# AT89S52_2.net
KiCad netlist of a schematic drawn in Altium Designer
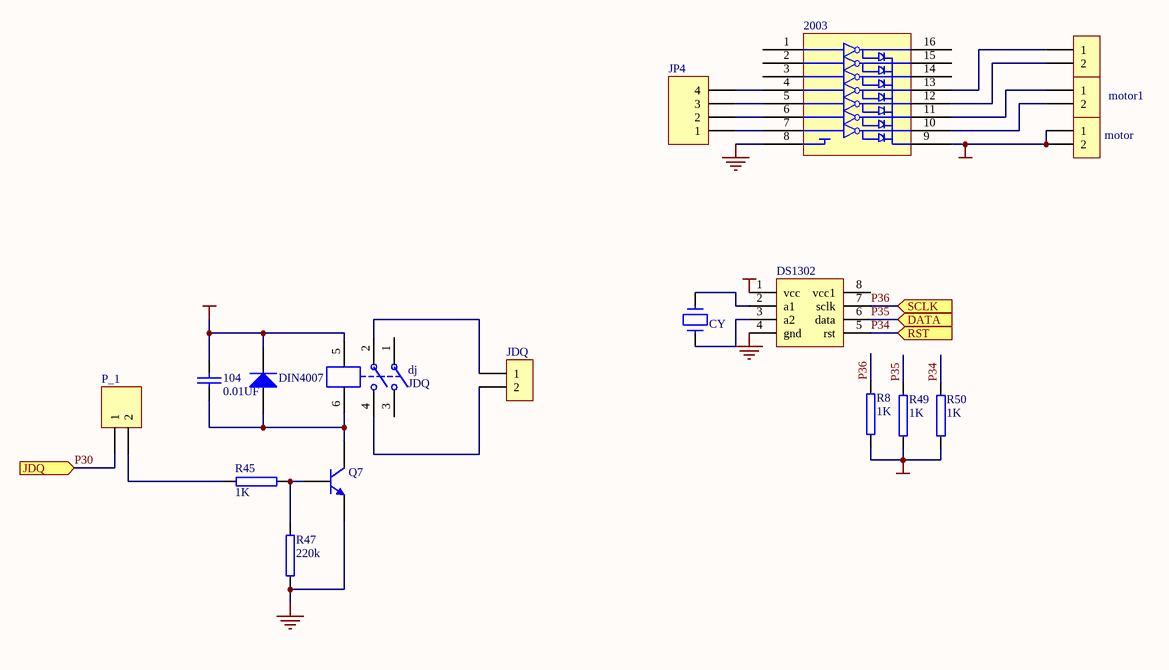
[diagram p0: AT89S52多功能板2.SchDoc]

(export (version "E")
  (design (tool "Eeschema 10.0.6"))
  (components
    (comp (ref "104")
      (value "0.01UF")
      (footprint "RAD0.3")
      (description "Capacitor")
      (libsource (lib "OldCow1 (1)") (part "CAP"))
    )
    (comp (ref "121") (value "CY") (footprint "CYPF") (libsource (lib "OldCow1 (1)") (part "CY")))
    (comp (ref "2003") (value "2003") (footprint "2003PF") (libsource (lib "OldCow1 (1)") (part "2003")))
    (comp (ref "DIN4007")
      (value "Diode 1N4007")
      (footprint "DO-41")
      (description "1 Amp General Purpose Rectifier")
      (fields (field (name "PUBLISHER") "Altium Limited"))
      (libsource (lib "Miscellaneous Devices") (part "Diode 1N4007"))
    )
    (comp (ref "dj") (value "JDQ") (footprint "JDQPF") (libsource (lib "OldCow1 (1)") (part "JDQ")))
    (comp (ref "DS1302") (value "DS1302") (footprint "DIP8") (libsource (lib "OldCow1 (1)") (part "DS1302")))
    (comp (ref "JDQ") (value "POWER") (footprint "POWERPF") (libsource (lib "OldCow1 (1)") (part "POWER")))
    (comp (ref "JP4")
      (value "Header 4")
      (footprint "HDR1X4")
      (description "Header, 4-Pin")
      (fields (field (name "PUBLISHER") "Altium Limited"))
      (libsource (lib "Miscellaneous Connectors") (part "Header 4"))
    )
    (comp (ref "motor") (value "POWER") (footprint "POWERPF") (libsource (lib "OldCow1 (1)") (part "POWER")))
    (comp (ref "motor1") (value "POWER") (footprint "POWERPF") (libsource (lib "OldCow1 (1)") (part "POWER")))
    (comp (ref "motor3") (value "POWER") (footprint "POWERPF") (libsource (lib "OldCow1 (1)") (part "POWER")))
    (comp (ref "P_1")
      (value "Header 2")
      (footprint "HDR1X2")
      (description "Header, 2-Pin")
      (fields (field (name "PUBLISHER") "Altium Limited"))
      (libsource (lib "Miscellaneous Connectors") (part "Header 2"))
    )
    (comp (ref "Q7")
      (value "2N3904")
      (footprint "TO-92A")
      (description "NPN General Purpose Amplifier")
      (fields (field (name "PUBLISHER") "Altium Limited"))
      (libsource (lib "Miscellaneous Devices") (part "2N3904"))
    )
    (comp (ref "R8") (value "1K") (footprint "RES1PF") (libsource (lib "OldCow1 (1)") (part "RES1")))
    (comp (ref "R45") (value "1K") (footprint "RES1PF") (libsource (lib "OldCow1 (1)") (part "RES1")))
    (comp (ref "R47") (value "220k") (footprint "AXIAL0.4") (libsource (lib "OldCow1 (1)") (part "RES2")))
    (comp (ref "R49") (value "1K") (footprint "RES1PF") (libsource (lib "OldCow1 (1)") (part "RES1")))
    (comp (ref "R50") (value "1K") (footprint "RES1PF") (libsource (lib "OldCow1 (1)") (part "RES1")))
  )
  (nets
    (net (code "1") (name "/P30") (class "Default")
      (node (ref "P_1") (pin "1") (pinfunction "1_1") (pintype "passive"))
    )
    (net (code "2") (name "/P34") (class "Default")
      (node (ref "DS1302") (pin "5") (pinfunction "rst_5") (pintype "passive"))
      (node (ref "R50") (pin "1") (pinfunction "1_1") (pintype "passive"))
    )
    (net (code "3") (name "/P35") (class "Default")
      (node (ref "DS1302") (pin "6") (pinfunction "data_6") (pintype "passive"))
      (node (ref "R49") (pin "1") (pinfunction "1_1") (pintype "passive"))
    )
    (net (code "4") (name "/P36") (class "Default")
      (node (ref "DS1302") (pin "7") (pinfunction "sclk_7") (pintype "passive"))
      (node (ref "R8") (pin "1") (pinfunction "1_1") (pintype "passive"))
    )
    (net (code "5") (name "GND") (class "Default")
      (node (ref "2003") (pin "8") (pinfunction "8_8") (pintype "passive"))
      (node (ref "DS1302") (pin "4") (pinfunction "gnd_4") (pintype "passive"))
      (node (ref "Q7") (pin "1") (pinfunction "E_1") (pintype "passive"))
      (node (ref "R47") (pin "1") (pinfunction "1_1") (pintype "passive"))
    )
    (net (code "6") (name "Net-(2003-Pad4)") (class "Default")
      (node (ref "2003") (pin "4") (pinfunction "4_4") (pintype "passive"))
      (node (ref "JP4") (pin "4") (pinfunction "4_4") (pintype "passive"))
    )
    (net (code "7") (name "Net-(2003-Pad5)") (class "Default")
      (node (ref "2003") (pin "5") (pinfunction "5_5") (pintype "passive"))
      (node (ref "JP4") (pin "3") (pinfunction "3_3") (pintype "passive"))
    )
    (net (code "8") (name "Net-(2003-Pad6)") (class "Default")
      (node (ref "2003") (pin "6") (pinfunction "6_6") (pintype "passive"))
      (node (ref "JP4") (pin "2") (pinfunction "2_2") (pintype "passive"))
    )
    (net (code "9") (name "Net-(2003-Pad7)") (class "Default")
      (node (ref "2003") (pin "7") (pinfunction "7_7") (pintype "passive"))
      (node (ref "JP4") (pin "1") (pinfunction "1_1") (pintype "passive"))
    )
    (net (code "10") (name "Net-(2003-Pad10)") (class "Default")
      (node (ref "2003") (pin "10") (pinfunction "10_10") (pintype "passive"))
      (node (ref "motor1") (pin "2") (pinfunction "2_2") (pintype "passive"))
    )
    (net (code "11") (name "Net-(2003-Pad11)") (class "Default")
      (node (ref "2003") (pin "11") (pinfunction "11_11") (pintype "passive"))
      (node (ref "motor1") (pin "1") (pinfunction "1_1") (pintype "passive"))
    )
    (net (code "12") (name "Net-(2003-Pad12)") (class "Default")
      (node (ref "2003") (pin "12") (pinfunction "12_12") (pintype "passive"))
      (node (ref "motor3") (pin "2") (pinfunction "2_2") (pintype "passive"))
    )
    (net (code "13") (name "Net-(2003-Pad13)") (class "Default")
      (node (ref "2003") (pin "13") (pinfunction "13_13") (pintype "passive"))
      (node (ref "motor3") (pin "1") (pinfunction "1_1") (pintype "passive"))
    )
    (net (code "14") (name "Net-(DIN4007-A)") (class "Default")
      (node (ref "104") (pin "2") (pinfunction "2_2") (pintype "passive"))
      (node (ref "DIN4007") (pin "1") (pinfunction "A_1") (pintype "passive"))
      (node (ref "Q7") (pin "3") (pinfunction "C_3") (pintype "passive"))
      (node (ref "dj") (pin "6") (pinfunction "6_6") (pintype "passive"))
    )
    (net (code "15") (name "Net-(DS1302-a1)") (class "Default")
      (node (ref "121") (pin "2") (pinfunction "2_2") (pintype "passive"))
      (node (ref "DS1302") (pin "2") (pinfunction "a1_2") (pintype "passive"))
    )
    (net (code "16") (name "Net-(DS1302-a2)") (class "Default")
      (node (ref "121") (pin "1") (pinfunction "1_1") (pintype "passive"))
      (node (ref "DS1302") (pin "3") (pinfunction "a2_3") (pintype "passive"))
    )
    (net (code "17") (name "Net-(JDQ-Pad1)") (class "Default")
      (node (ref "JDQ") (pin "1") (pinfunction "1_1") (pintype "passive"))
      (node (ref "dj") (pin "2") (pinfunction "2_2") (pintype "passive"))
    )
    (net (code "18") (name "Net-(JDQ-Pad2)") (class "Default")
      (node (ref "JDQ") (pin "2") (pinfunction "2_2") (pintype "passive"))
      (node (ref "dj") (pin "4") (pinfunction "4_4") (pintype "passive"))
    )
    (net (code "19") (name "Net-(P_1-Pad2)") (class "Default")
      (node (ref "P_1") (pin "2") (pinfunction "2_2") (pintype "passive"))
      (node (ref "R45") (pin "2") (pinfunction "2_2") (pintype "passive"))
    )
    (net (code "20") (name "Net-(Q7-B)") (class "Default")
      (node (ref "Q7") (pin "2") (pinfunction "B_2") (pintype "passive"))
      (node (ref "R45") (pin "1") (pinfunction "1_1") (pintype "passive"))
      (node (ref "R47") (pin "2") (pinfunction "2_2") (pintype "passive"))
    )
    (net (code "21") (name "VCC") (class "Default")
      (node (ref "104") (pin "1") (pinfunction "1_1") (pintype "passive"))
      (node (ref "2003") (pin "9") (pinfunction "9_9") (pintype "passive"))
      (node (ref "DIN4007") (pin "2") (pinfunction "K_2") (pintype "passive"))
      (node (ref "DS1302") (pin "1") (pinfunction "vcc_1") (pintype "passive"))
      (node (ref "R49") (pin "2") (pinfunction "2_2") (pintype "passive"))
      (node (ref "R50") (pin "2") (pinfunction "2_2") (pintype "passive"))
      (node (ref "R8") (pin "2") (pinfunction "2_2") (pintype "passive"))
      (node (ref "dj") (pin "5") (pinfunction "5_5") (pintype "passive"))
      (node (ref "motor") (pin "1") (pinfunction "1_1") (pintype "passive"))
      (node (ref "motor") (pin "2") (pinfunction "2_2") (pintype "passive"))
    )
    (net (code "22") (name "unconnected-(2003-Pad1)") (class "Default")
      (node (ref "2003") (pin "1") (pinfunction "1_1") (pintype "passive"))
    )
    (net (code "23") (name "unconnected-(2003-Pad2)") (class "Default")
      (node (ref "2003") (pin "2") (pinfunction "2_2") (pintype "passive"))
    )
    (net (code "24") (name "unconnected-(2003-Pad3)") (class "Default")
      (node (ref "2003") (pin "3") (pintype "passive"))
    )
    (net (code "25") (name "unconnected-(2003-Pad14)") (class "Default")
      (node (ref "2003") (pin "14") (pinfunction "14_14") (pintype "passive"))
    )
    (net (code "26") (name "unconnected-(2003-Pad15)") (class "Default")
      (node (ref "2003") (pin "15") (pinfunction "15_15") (pintype "passive"))
    )
    (net (code "27") (name "unconnected-(2003-Pad16)") (class "Default")
      (node (ref "2003") (pin "16") (pinfunction "16_16") (pintype "passive"))
    )
    (net (code "28") (name "unconnected-(DS1302-vcc1-Pad8)") (class "Default")
      (node (ref "DS1302") (pin "8") (pinfunction "vcc1_8") (pintype "passive"))
    )
    (net (code "29") (name "unconnected-(dj-Pad1)") (class "Default")
      (node (ref "dj") (pin "1") (pinfunction "1_1") (pintype "passive"))
    )
    (net (code "30") (name "unconnected-(dj-Pad3)") (class "Default")
      (node (ref "dj") (pin "3") (pinfunction "3_3") (pintype "passive"))
    )
  )
)
